# tm7_revE.net
KiCad netlist of a schematic drawn in EAGLE
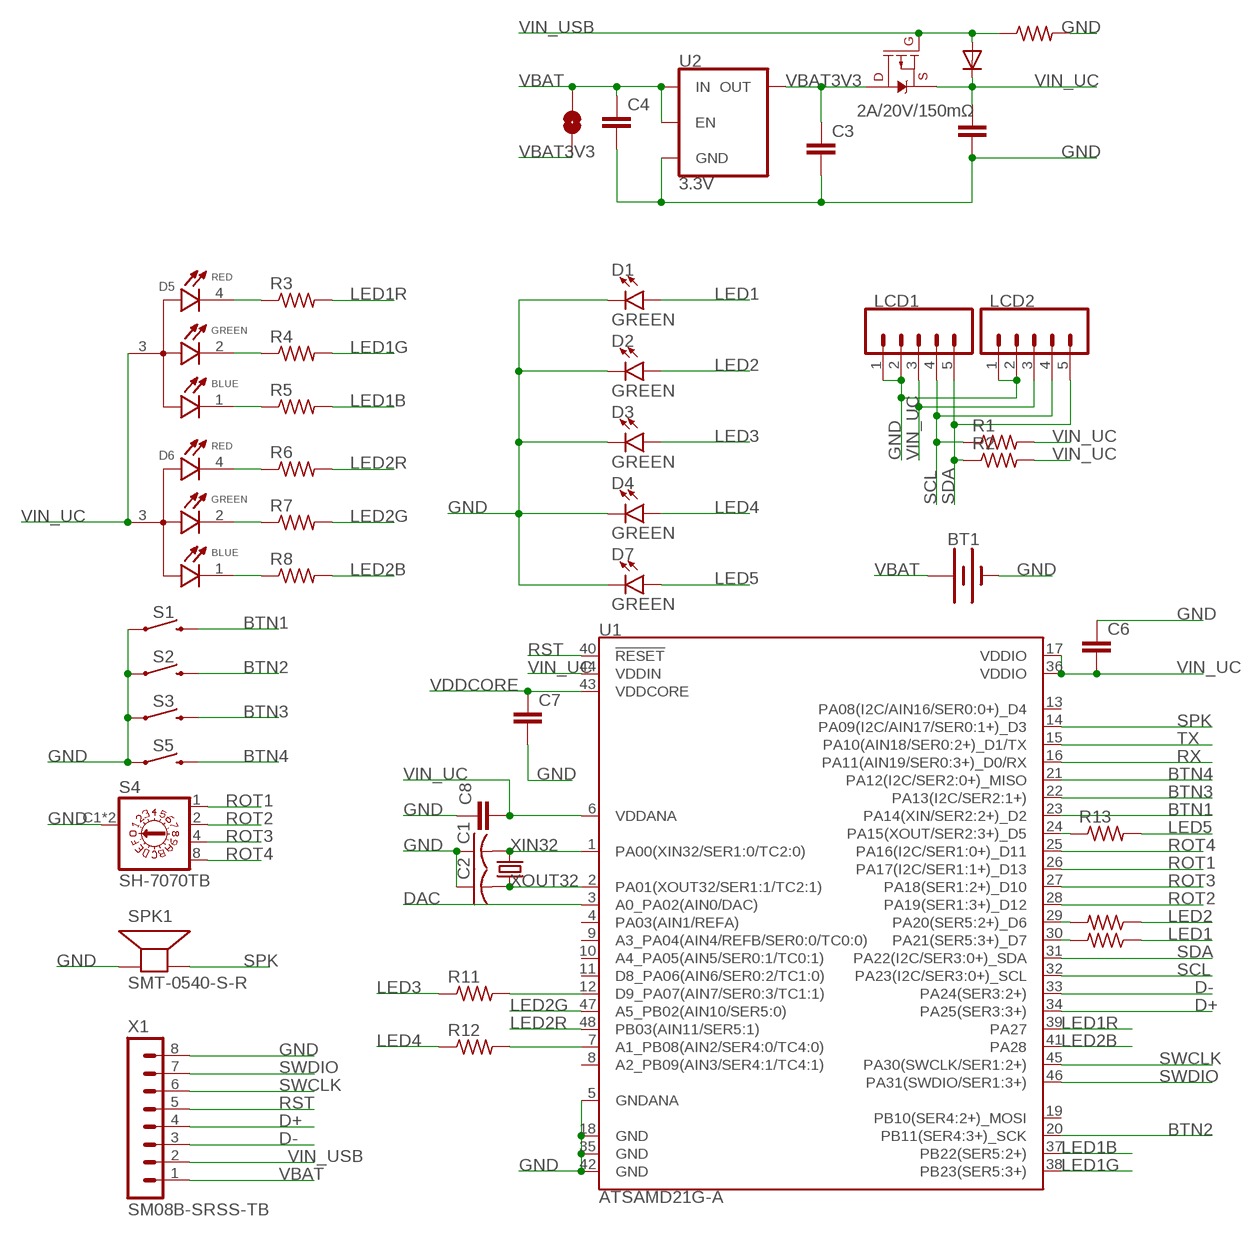
[diagram p0: schematic, sheet 1]

(export (version "E")
  (design (tool "Eeschema 10.0.6"))
  (components
    (comp (ref "BT1")
      (value "BATTERY-20MM_SMD_4LEGS_OVERPASTE_INNER")
      (footprint "eagle-import:BATTCON_20MM_4LEGS_OVERPASTE_INNER")
      (libsource (lib "eagle-import") (part "BATTERY-20MM_SMD_4LEGS_OVERPASTE_INNER"))
    )
    (comp (ref "C1")
      (value "C-USC0603")
      (footprint "eagle-import:C0603")
      (libsource (lib "eagle-import") (part "C-USC0603"))
    )
    (comp (ref "C2")
      (value "C-USC0603")
      (footprint "eagle-import:C0603")
      (libsource (lib "eagle-import") (part "C-USC0603"))
    )
    (comp (ref "C3")
      (value "C-EUC0603")
      (footprint "eagle-import:C0603")
      (libsource (lib "eagle-import") (part "C-EUC0603"))
    )
    (comp (ref "C4")
      (value "C-EUC0603")
      (footprint "eagle-import:C0603")
      (libsource (lib "eagle-import") (part "C-EUC0603"))
    )
    (comp (ref "C6")
      (value "C-EUC0603")
      (footprint "eagle-import:C0603")
      (libsource (lib "eagle-import") (part "C-EUC0603"))
    )
    (comp (ref "C7")
      (value "C-EUC0603")
      (footprint "eagle-import:C0603")
      (libsource (lib "eagle-import") (part "C-EUC0603"))
    )
    (comp (ref "C8")
      (value "C-EUC0603")
      (footprint "eagle-import:C0603")
      (libsource (lib "eagle-import") (part "C-EUC0603"))
    )
    (comp (ref "C9")
      (value "C-EUC0603")
      (footprint "eagle-import:C0603")
      (libsource (lib "eagle-import") (part "C-EUC0603"))
    )
    (comp (ref "D1")
      (value "GREEN")
      (footprint "eagle-import:LED-1206")
      (libsource (lib "eagle-import") (part "LED-GREEN1206"))
    )
    (comp (ref "D2")
      (value "GREEN")
      (footprint "eagle-import:LED-1206")
      (libsource (lib "eagle-import") (part "LED-GREEN1206"))
    )
    (comp (ref "D3")
      (value "GREEN")
      (footprint "eagle-import:LED-1206")
      (libsource (lib "eagle-import") (part "LED-GREEN1206"))
    )
    (comp (ref "D4")
      (value "GREEN")
      (footprint "eagle-import:LED-1206")
      (libsource (lib "eagle-import") (part "LED-GREEN1206"))
    )
    (comp (ref "D5")
      (value "EAST1616RGBA3")
      (footprint "eagle-import:LED_EAST1616RGBA3")
      (fields (field (name "MF") "Everlight Electronics"))
      (libsource (lib "eagle-import") (part "EAST1616RGBA3"))
    )
    (comp (ref "D6")
      (value "EAST1616RGBA3")
      (footprint "eagle-import:LED_EAST1616RGBA3")
      (fields (field (name "MF") "Everlight Electronics"))
      (libsource (lib "eagle-import") (part "EAST1616RGBA3"))
    )
    (comp (ref "D7")
      (value "GREEN")
      (footprint "eagle-import:LED-1206")
      (libsource (lib "eagle-import") (part "LED-GREEN1206"))
    )
    (comp (ref "D8")
      (value "DIODESOD-323F")
      (footprint "eagle-import:SOD-323F")
      (libsource (lib "eagle-import") (part "DIODESOD-323F"))
    )
    (comp (ref "JP1")
      (value "JUMPER-SMT_2_NO_NO-SILK")
      (footprint "eagle-import:SMT-JUMPER_2_NO_NO-SILK")
      (libsource (lib "eagle-import") (part "JUMPER-SMT_2_NO_NO-SILK"))
    )
    (comp (ref "LCD1")
      (value "CONN_05VERT_FEMALE_HEADER")
      (footprint "eagle-import:1X05_SMD_VERTICAL_COMBO")
      (libsource (lib "eagle-import") (part "CONN_05VERT_FEMALE_HEADER"))
    )
    (comp (ref "LCD2")
      (value "CONN_05VERT_FEMALE_HEADER")
      (footprint "eagle-import:1X05_SMD_VERTICAL_COMBO")
      (libsource (lib "eagle-import") (part "CONN_05VERT_FEMALE_HEADER"))
    )
    (comp (ref "Q1")
      (value "2A/20V/150mΩ")
      (footprint "eagle-import:SOT26")
      (libsource (lib "eagle-import") (part "MOSFET_PCH_DUAL-DMP2240UDM"))
    )
    (comp (ref "R1")
      (value "R-US_R0603")
      (footprint "eagle-import:R0603")
      (libsource (lib "eagle-import") (part "rcl_334_R-US_R0603"))
    )
    (comp (ref "R2")
      (value "R-US_R0603")
      (footprint "eagle-import:R0603")
      (libsource (lib "eagle-import") (part "rcl_334_R-US_R0603"))
    )
    (comp (ref "R3")
      (value "R-US_R0603")
      (footprint "eagle-import:R0603")
      (libsource (lib "eagle-import") (part "rcl_334_R-US_R0603"))
    )
    (comp (ref "R4")
      (value "R-US_R0603")
      (footprint "eagle-import:R0603")
      (libsource (lib "eagle-import") (part "rcl_334_R-US_R0603"))
    )
    (comp (ref "R5")
      (value "R-US_R0603")
      (footprint "eagle-import:R0603")
      (libsource (lib "eagle-import") (part "rcl_334_R-US_R0603"))
    )
    (comp (ref "R6")
      (value "R-US_R0603")
      (footprint "eagle-import:R0603")
      (libsource (lib "eagle-import") (part "rcl_334_R-US_R0603"))
    )
    (comp (ref "R7")
      (value "R-US_R0603")
      (footprint "eagle-import:R0603")
      (libsource (lib "eagle-import") (part "rcl_334_R-US_R0603"))
    )
    (comp (ref "R8")
      (value "R-US_R0603")
      (footprint "eagle-import:R0603")
      (libsource (lib "eagle-import") (part "rcl_334_R-US_R0603"))
    )
    (comp (ref "R9")
      (value "R-US_R0603")
      (footprint "eagle-import:R0603")
      (libsource (lib "eagle-import") (part "rcl_334_R-US_R0603"))
    )
    (comp (ref "R10")
      (value "R-US_R0603")
      (footprint "eagle-import:R0603")
      (libsource (lib "eagle-import") (part "rcl_334_R-US_R0603"))
    )
    (comp (ref "R11")
      (value "R-US_R0603")
      (footprint "eagle-import:R0603")
      (libsource (lib "eagle-import") (part "rcl_334_R-US_R0603"))
    )
    (comp (ref "R12")
      (value "R-US_R0603")
      (footprint "eagle-import:R0603")
      (libsource (lib "eagle-import") (part "rcl_334_R-US_R0603"))
    )
    (comp (ref "R13")
      (value "R-US_R0603")
      (footprint "eagle-import:R0603")
      (libsource (lib "eagle-import") (part "rcl_334_R-US_R0603"))
    )
    (comp (ref "R14")
      (value "R-US_R0603")
      (footprint "eagle-import:R0603")
      (libsource (lib "eagle-import") (part "R-US_R0603"))
    )
    (comp (ref "S1")
      (value "MOMENTARY-SWITCH-SPST-SMD-6.0X3.5MM")
      (footprint "eagle-import:TACTILE_SWITCH_SMD_6.0X3.5MM")
      (libsource (lib "eagle-import") (part "MOMENTARY-SWITCH-SPST-SMD-6.0X3.5MM"))
    )
    (comp (ref "S2")
      (value "MOMENTARY-SWITCH-SPST-SMD-6.0X3.5MM")
      (footprint "eagle-import:TACTILE_SWITCH_SMD_6.0X3.5MM")
      (libsource (lib "eagle-import") (part "MOMENTARY-SWITCH-SPST-SMD-6.0X3.5MM"))
    )
    (comp (ref "S3")
      (value "MOMENTARY-SWITCH-SPST-SMD-6.0X3.5MM")
      (footprint "eagle-import:TACTILE_SWITCH_SMD_6.0X3.5MM")
      (libsource (lib "eagle-import") (part "MOMENTARY-SWITCH-SPST-SMD-6.0X3.5MM"))
    )
    (comp (ref "S4")
      (value "SH-7070TB")
      (footprint "eagle-import:SH-7070B")
      (fields (field (name "MF") "Nidec Copal"))
      (libsource (lib "eagle-import") (part "SH-7070TB"))
    )
    (comp (ref "S5")
      (value "MOMENTARY-SWITCH-SPST-SMD-6.0X3.5MM")
      (footprint "eagle-import:TACTILE_SWITCH_SMD_6.0X3.5MM")
      (libsource (lib "eagle-import") (part "MOMENTARY-SWITCH-SPST-SMD-6.0X3.5MM"))
    )
    (comp (ref "SPK1")
      (value "SMT-0540-S-R")
      (footprint "eagle-import:SMT-0540-S-R")
      (fields (field (name "MF") "PUI"))
      (libsource (lib "eagle-import") (part "SMT-0540-S-R"))
    )
    (comp (ref "U1")
      (value "ATSAMD21G-A")
      (footprint "eagle-import:TQFP-48")
      (libsource (lib "eagle-import") (part "ATSAMD21G-A"))
    )
    (comp (ref "U2")
      (value "3.3V")
      (footprint "eagle-import:SOT23-5")
      (libsource (lib "eagle-import") (part "V_REG_AP2112K-3.3V"))
    )
    (comp (ref "X1")
      (value "SM08B-SRSS-TB")
      (footprint "eagle-import:SM08B-SRSS-TB")
      (libsource (lib "eagle-import") (part "SM08B-SRSS-TB"))
    )
    (comp (ref "Y1")
      (value "32.768kHz")
      (footprint "eagle-import:CRYSTAL-SMD-3.2X1.5MM")
      (libsource (lib "eagle-import") (part "CRYSTAL-32.768KHZSMD-3.2X1.5"))
    )
  )
  (nets
    (net (code "1") (name "/BTN1") (class "Default")
      (node (ref "S1") (pin "2") (pinfunction "2_2") (pintype "passive"))
      (node (ref "U1") (pin "23") (pinfunction "PA14(XIN/SER2:2+)_D2_23") (pintype "bidirectional"))
    )
    (net (code "2") (name "/BTN2") (class "Default")
      (node (ref "S2") (pin "2") (pinfunction "2_2") (pintype "passive"))
      (node (ref "U1") (pin "20") (pinfunction "PB11(SER4:3+)_SCK_20") (pintype "bidirectional"))
    )
    (net (code "3") (name "/BTN3") (class "Default")
      (node (ref "S3") (pin "2") (pinfunction "2_2") (pintype "passive"))
      (node (ref "U1") (pin "22") (pinfunction "PA13(I2C/SER2:1+)_22") (pintype "bidirectional"))
    )
    (net (code "4") (name "/BTN4") (class "Default")
      (node (ref "S5") (pin "2") (pinfunction "2_2") (pintype "passive"))
      (node (ref "U1") (pin "21") (pinfunction "PA12(I2C/SER2:0+)_MISO_21") (pintype "bidirectional"))
    )
    (net (code "5") (name "/D+") (class "Default")
      (node (ref "U1") (pin "34") (pinfunction "PA25(SER3:3+)_34") (pintype "bidirectional"))
      (node (ref "X1") (pin "4") (pinfunction "4_4") (pintype "passive"))
    )
    (net (code "6") (name "/D-") (class "Default")
      (node (ref "U1") (pin "33") (pinfunction "PA24(SER3:2+)_33") (pintype "bidirectional"))
      (node (ref "X1") (pin "3") (pinfunction "3_3") (pintype "passive"))
    )
    (net (code "7") (name "/DAC") (class "Default")
      (node (ref "U1") (pin "3") (pinfunction "A0_PA02(AIN0/DAC)_3") (pintype "bidirectional"))
    )
    (net (code "8") (name "/GND") (class "Default")
      (node (ref "BT1") (pin "2") (pinfunction "-_2") (pintype "power_in"))
      (node (ref "C1") (pin "1") (pinfunction "1_1") (pintype "passive"))
      (node (ref "C2") (pin "1") (pinfunction "1_1") (pintype "passive"))
      (node (ref "C3") (pin "2") (pinfunction "2_2") (pintype "passive"))
      (node (ref "C4") (pin "2") (pinfunction "2_2") (pintype "passive"))
      (node (ref "C6") (pin "1") (pinfunction "1_1") (pintype "passive"))
      (node (ref "C7") (pin "2") (pinfunction "2_2") (pintype "passive"))
      (node (ref "C8") (pin "1") (pinfunction "1_1") (pintype "passive"))
      (node (ref "C9") (pin "2") (pinfunction "2_2") (pintype "passive"))
      (node (ref "D1") (pin "C") (pinfunction "C_C") (pintype "passive"))
      (node (ref "D2") (pin "C") (pinfunction "C_C") (pintype "passive"))
      (node (ref "D3") (pin "C") (pinfunction "C_C") (pintype "passive"))
      (node (ref "D4") (pin "C") (pinfunction "C_C") (pintype "passive"))
      (node (ref "D7") (pin "C") (pinfunction "C_C") (pintype "passive"))
      (node (ref "LCD1") (pin "1") (pinfunction "1_1") (pintype "passive"))
      (node (ref "LCD1") (pin "2") (pinfunction "2_2") (pintype "passive"))
      (node (ref "LCD2") (pin "1") (pinfunction "1_1") (pintype "passive"))
      (node (ref "LCD2") (pin "2") (pinfunction "2_2") (pintype "passive"))
      (node (ref "R14") (pin "2") (pinfunction "2_2") (pintype "passive"))
      (node (ref "S1") (pin "1") (pinfunction "1_1") (pintype "passive"))
      (node (ref "S2") (pin "1") (pinfunction "1_1") (pintype "passive"))
      (node (ref "S3") (pin "1") (pinfunction "1_1") (pintype "passive"))
      (node (ref "S4") (pin "C1") (pinfunction "C_C1") (pintype "passive"))
      (node (ref "S4") (pin "C2") (pinfunction "C_C2") (pintype "passive"))
      (node (ref "S5") (pin "1") (pinfunction "1_1") (pintype "passive"))
      (node (ref "SPK1") (pin "-") (pinfunction "+_-") (pintype "passive"))
      (node (ref "U1") (pin "18") (pinfunction "GND_18") (pintype "bidirectional"))
      (node (ref "U1") (pin "35") (pinfunction "GND_35") (pintype "bidirectional"))
      (node (ref "U1") (pin "42") (pinfunction "GND_42") (pintype "bidirectional"))
      (node (ref "U1") (pin "5") (pinfunction "GNDANA_5") (pintype "bidirectional"))
      (node (ref "U2") (pin "2") (pinfunction "GND_2") (pintype "input"))
      (node (ref "X1") (pin "8") (pinfunction "8_8") (pintype "passive"))
    )
    (net (code "9") (name "/LED1") (class "Default")
      (node (ref "D1") (pin "A") (pinfunction "A_A") (pintype "passive"))
      (node (ref "R9") (pin "1") (pinfunction "1_1") (pintype "passive"))
    )
    (net (code "10") (name "/LED1B") (class "Default")
      (node (ref "R5") (pin "2") (pinfunction "2_2") (pintype "passive"))
      (node (ref "U1") (pin "37") (pinfunction "PB22(SER5:2+)_37") (pintype "bidirectional"))
    )
    (net (code "11") (name "/LED1G") (class "Default")
      (node (ref "R4") (pin "2") (pinfunction "2_2") (pintype "passive"))
      (node (ref "U1") (pin "38") (pinfunction "PB23(SER5:3+)_38") (pintype "bidirectional"))
    )
    (net (code "12") (name "/LED1R") (class "Default")
      (node (ref "R3") (pin "2") (pinfunction "2_2") (pintype "passive"))
      (node (ref "U1") (pin "39") (pinfunction "PA27_39") (pintype "bidirectional"))
    )
    (net (code "13") (name "/LED2") (class "Default")
      (node (ref "D2") (pin "A") (pinfunction "A_A") (pintype "passive"))
      (node (ref "R10") (pin "1") (pinfunction "1_1") (pintype "passive"))
    )
    (net (code "14") (name "/LED2B") (class "Default")
      (node (ref "R8") (pin "2") (pinfunction "2_2") (pintype "passive"))
      (node (ref "U1") (pin "41") (pinfunction "PA28_41") (pintype "bidirectional"))
    )
    (net (code "15") (name "/LED2G") (class "Default")
      (node (ref "R7") (pin "2") (pinfunction "2_2") (pintype "passive"))
      (node (ref "U1") (pin "47") (pinfunction "A5_PB02(AIN10/SER5:0)_47") (pintype "bidirectional"))
    )
    (net (code "16") (name "/LED2R") (class "Default")
      (node (ref "R6") (pin "2") (pinfunction "2_2") (pintype "passive"))
      (node (ref "U1") (pin "48") (pinfunction "PB03(AIN11/SER5:1)_48") (pintype "bidirectional"))
    )
    (net (code "17") (name "/LED3") (class "Default")
      (node (ref "D3") (pin "A") (pinfunction "A_A") (pintype "passive"))
      (node (ref "R11") (pin "1") (pinfunction "1_1") (pintype "passive"))
    )
    (net (code "18") (name "/LED4") (class "Default")
      (node (ref "D4") (pin "A") (pinfunction "A_A") (pintype "passive"))
      (node (ref "R12") (pin "1") (pinfunction "1_1") (pintype "passive"))
    )
    (net (code "19") (name "/LED5") (class "Default")
      (node (ref "D7") (pin "A") (pinfunction "A_A") (pintype "passive"))
      (node (ref "R13") (pin "2") (pinfunction "2_2") (pintype "passive"))
    )
    (net (code "20") (name "/ROT1") (class "Default")
      (node (ref "S4") (pin "1") (pinfunction "1_1") (pintype "passive"))
      (node (ref "U1") (pin "26") (pinfunction "PA17(I2C/SER1:1+)_D13_26") (pintype "bidirectional"))
    )
    (net (code "21") (name "/ROT2") (class "Default")
      (node (ref "S4") (pin "2") (pinfunction "2_2") (pintype "passive"))
      (node (ref "U1") (pin "28") (pinfunction "PA19(SER1:3+)_D12_28") (pintype "bidirectional"))
    )
    (net (code "22") (name "/ROT3") (class "Default")
      (node (ref "S4") (pin "4") (pinfunction "4_4") (pintype "passive"))
      (node (ref "U1") (pin "27") (pinfunction "PA18(SER1:2+)_D10_27") (pintype "bidirectional"))
    )
    (net (code "23") (name "/ROT4") (class "Default")
      (node (ref "S4") (pin "8") (pinfunction "8_8") (pintype "passive"))
      (node (ref "U1") (pin "25") (pinfunction "PA16(I2C/SER1:0+)_D11_25") (pintype "bidirectional"))
    )
    (net (code "24") (name "/RST") (class "Default")
      (node (ref "U1") (pin "40") (pinfunction "~{RESET}_40") (pintype "bidirectional"))
      (node (ref "X1") (pin "5") (pinfunction "5_5") (pintype "passive"))
    )
    (net (code "25") (name "/RX") (class "Default")
      (node (ref "U1") (pin "16") (pinfunction "PA11(AIN19/SER0:3+)_D0/RX_16") (pintype "bidirectional"))
    )
    (net (code "26") (name "/SCL") (class "Default")
      (node (ref "LCD1") (pin "4") (pinfunction "4_4") (pintype "passive"))
      (node (ref "LCD2") (pin "4") (pinfunction "4_4") (pintype "passive"))
      (node (ref "R1") (pin "1") (pinfunction "1_1") (pintype "passive"))
      (node (ref "U1") (pin "32") (pinfunction "PA23(I2C/SER3:0+)_SCL_32") (pintype "bidirectional"))
    )
    (net (code "27") (name "/SDA") (class "Default")
      (node (ref "LCD1") (pin "5") (pinfunction "5_5") (pintype "passive"))
      (node (ref "LCD2") (pin "5") (pinfunction "5_5") (pintype "passive"))
      (node (ref "R2") (pin "1") (pinfunction "1_1") (pintype "passive"))
      (node (ref "U1") (pin "31") (pinfunction "PA22(I2C/SER3:0+)_SDA_31") (pintype "bidirectional"))
    )
    (net (code "28") (name "/SPK") (class "Default")
      (node (ref "SPK1") (pin "+") (pinfunction "-_+") (pintype "passive"))
      (node (ref "U1") (pin "14") (pinfunction "PA09(I2C/AIN17/SER0:1+)_D3_14") (pintype "bidirectional"))
    )
    (net (code "29") (name "/SWCLK") (class "Default")
      (node (ref "U1") (pin "45") (pinfunction "PA30(SWCLK/SER1:2+)_45") (pintype "bidirectional"))
      (node (ref "X1") (pin "6") (pinfunction "6_6") (pintype "passive"))
    )
    (net (code "30") (name "/SWDIO") (class "Default")
      (node (ref "U1") (pin "46") (pinfunction "PA31(SWDIO/SER1:3+)_46") (pintype "bidirectional"))
      (node (ref "X1") (pin "7") (pinfunction "7_7") (pintype "passive"))
    )
    (net (code "31") (name "/TX") (class "Default")
      (node (ref "U1") (pin "15") (pinfunction "PA10(AIN18/SER0:2+)_D1/TX_15") (pintype "bidirectional"))
    )
    (net (code "32") (name "/VBAT") (class "Default")
      (node (ref "BT1") (pin "1") (pinfunction "+_1") (pintype "power_in"))
      (node (ref "C4") (pin "1") (pinfunction "1_1") (pintype "passive"))
      (node (ref "JP1") (pin "2") (pinfunction "2_2") (pintype "passive"))
      (node (ref "U2") (pin "1") (pinfunction "IN_1") (pintype "input"))
      (node (ref "U2") (pin "3") (pinfunction "EN_3") (pintype "input"))
      (node (ref "X1") (pin "1") (pinfunction "1_1") (pintype "passive"))
    )
    (net (code "33") (name "/VBAT3V3") (class "Default")
      (node (ref "C3") (pin "1") (pinfunction "1_1") (pintype "passive"))
      (node (ref "JP1") (pin "1") (pinfunction "1_1") (pintype "passive"))
      (node (ref "Q1") (pin "D1") (pinfunction "D_D1") (pintype "bidirectional"))
      (node (ref "U2") (pin "5") (pinfunction "OUT_5") (pintype "passive"))
    )
    (net (code "34") (name "/VDDCORE") (class "Default")
      (node (ref "C7") (pin "1") (pinfunction "1_1") (pintype "passive"))
      (node (ref "U1") (pin "43") (pinfunction "VDDCORE_43") (pintype "bidirectional"))
    )
    (net (code "35") (name "/VIN_UC") (class "Default")
      (node (ref "C6") (pin "2") (pinfunction "2_2") (pintype "passive"))
      (node (ref "C8") (pin "2") (pinfunction "2_2") (pintype "passive"))
      (node (ref "C9") (pin "1") (pinfunction "1_1") (pintype "passive"))
      (node (ref "D5") (pin "3") (pinfunction "A_3") (pintype "passive"))
      (node (ref "D6") (pin "3") (pinfunction "A_3") (pintype "passive"))
      (node (ref "D8") (pin "C") (pinfunction "C_C") (pintype "passive"))
      (node (ref "LCD1") (pin "3") (pinfunction "3_3") (pintype "passive"))
      (node (ref "LCD2") (pin "3") (pinfunction "3_3") (pintype "passive"))
      (node (ref "Q1") (pin "S1") (pinfunction "S_S1") (pintype "bidirectional"))
      (node (ref "R1") (pin "2") (pinfunction "2_2") (pintype "passive"))
      (node (ref "R2") (pin "2") (pinfunction "2_2") (pintype "passive"))
      (node (ref "U1") (pin "17") (pinfunction "VDDIO_17") (pintype "bidirectional"))
      (node (ref "U1") (pin "36") (pinfunction "VDDIO_36") (pintype "bidirectional"))
      (node (ref "U1") (pin "44") (pinfunction "VDDIN_44") (pintype "bidirectional"))
      (node (ref "U1") (pin "6") (pinfunction "VDDANA_6") (pintype "bidirectional"))
    )
    (net (code "36") (name "/VIN_USB") (class "Default")
      (node (ref "D8") (pin "A") (pinfunction "A_A") (pintype "passive"))
      (node (ref "Q1") (pin "G1") (pinfunction "G_G1") (pintype "bidirectional"))
      (node (ref "R14") (pin "1") (pinfunction "1_1") (pintype "passive"))
      (node (ref "X1") (pin "2") (pinfunction "2_2") (pintype "passive"))
    )
    (net (code "37") (name "/XIN32") (class "Default")
      (node (ref "C1") (pin "2") (pinfunction "2_2") (pintype "passive"))
      (node (ref "U1") (pin "1") (pinfunction "PA00(XIN32/SER1:0/TC2:0)_1") (pintype "bidirectional"))
      (node (ref "Y1") (pin "P$2") (pinfunction "2_P$2") (pintype "passive"))
    )
    (net (code "38") (name "/XOUT32") (class "Default")
      (node (ref "C2") (pin "2") (pinfunction "2_2") (pintype "passive"))
      (node (ref "U1") (pin "2") (pinfunction "PA01(XOUT32/SER1:1/TC2:1)_2") (pintype "bidirectional"))
      (node (ref "Y1") (pin "P$1") (pinfunction "1_P$1") (pintype "passive"))
    )
    (net (code "39") (name "Net-(D5-B_C)") (class "Default")
      (node (ref "D5") (pin "1") (pinfunction "B_C_1") (pintype "passive"))
      (node (ref "R5") (pin "1") (pinfunction "1_1") (pintype "passive"))
    )
    (net (code "40") (name "Net-(D5-G_C)") (class "Default")
      (node (ref "D5") (pin "2") (pinfunction "G_C_2") (pintype "passive"))
      (node (ref "R4") (pin "1") (pinfunction "1_1") (pintype "passive"))
    )
    (net (code "41") (name "Net-(D5-R_C)") (class "Default")
      (node (ref "D5") (pin "4") (pinfunction "R_C_4") (pintype "passive"))
      (node (ref "R3") (pin "1") (pinfunction "1_1") (pintype "passive"))
    )
    (net (code "42") (name "Net-(D6-B_C)") (class "Default")
      (node (ref "D6") (pin "1") (pinfunction "B_C_1") (pintype "passive"))
      (node (ref "R8") (pin "1") (pinfunction "1_1") (pintype "passive"))
    )
    (net (code "43") (name "Net-(D6-G_C)") (class "Default")
      (node (ref "D6") (pin "2") (pinfunction "G_C_2") (pintype "passive"))
      (node (ref "R7") (pin "1") (pinfunction "1_1") (pintype "passive"))
    )
    (net (code "44") (name "Net-(D6-R_C)") (class "Default")
      (node (ref "D6") (pin "4") (pinfunction "R_C_4") (pintype "passive"))
      (node (ref "R6") (pin "1") (pinfunction "1_1") (pintype "passive"))
    )
    (net (code "45") (name "Net-(U1-A1_PB08(AIN2{slash}SER4:0{slash}TC4:0))") (class "Default")
      (node (ref "R12") (pin "2") (pinfunction "2_2") (pintype "passive"))
      (node (ref "U1") (pin "7") (pinfunction "A1_PB08(AIN2/SER4:0/TC4:0)_7") (pintype "bidirectional"))
    )
    (net (code "46") (name "Net-(U1-D9_PA07(AIN7{slash}SER0:3{slash}TC1:1))") (class "Default")
      (node (ref "R11") (pin "2") (pinfunction "2_2") (pintype "passive"))
      (node (ref "U1") (pin "12") (pinfunction "D9_PA07(AIN7/SER0:3/TC1:1)_12") (pintype "bidirectional"))
    )
    (net (code "47") (name "Net-(U1-PA15(XOUT{slash}SER2:3+)_D5)") (class "Default")
      (node (ref "R13") (pin "1") (pinfunction "1_1") (pintype "passive"))
      (node (ref "U1") (pin "24") (pinfunction "PA15(XOUT/SER2:3+)_D5_24") (pintype "bidirectional"))
    )
    (net (code "48") (name "Net-(U1-PA20(SER5:2+)_D6)") (class "Default")
      (node (ref "R10") (pin "2") (pinfunction "2_2") (pintype "passive"))
      (node (ref "U1") (pin "29") (pinfunction "PA20(SER5:2+)_D6_29") (pintype "bidirectional"))
    )
    (net (code "49") (name "Net-(U1-PA21(SER5:3+)_D7)") (class "Default")
      (node (ref "R9") (pin "2") (pinfunction "2_2") (pintype "passive"))
      (node (ref "U1") (pin "30") (pinfunction "PA21(SER5:3+)_D7_30") (pintype "bidirectional"))
    )
    (net (code "50") (name "unconnected-(U1-A2_PB09(AIN3{slash}SER4:1{slash}TC4:1)-Pad8)") (class "Default")
      (node (ref "U1") (pin "8") (pinfunction "A2_PB09(AIN3/SER4:1/TC4:1)_8") (pintype "bidirectional"))
    )
    (net (code "51") (name "unconnected-(U1-A3_PA04(AIN4{slash}REFB{slash}SER0:0{slash}TC0:0)-Pad9)") (class "Default")
      (node (ref "U1") (pin "9") (pinfunction "A3_PA04(AIN4/REFB/SER0:0/TC0:0)_9") (pintype "bidirectional"))
    )
    (net (code "52") (name "unconnected-(U1-A4_PA05(AIN5{slash}SER0:1{slash}TC0:1)-Pad10)") (class "Default")
      (node (ref "U1") (pin "10") (pinfunction "A4_PA05(AIN5/SER0:1/TC0:1)_10") (pintype "bidirectional"))
    )
    (net (code "53") (name "unconnected-(U1-D8_PA06(AIN6{slash}SER0:2{slash}TC1:0)-Pad11)") (class "Default")
      (node (ref "U1") (pin "11") (pinfunction "D8_PA06(AIN6/SER0:2/TC1:0)_11") (pintype "bidirectional"))
    )
    (net (code "54") (name "unconnected-(U1-PA03(AIN1{slash}REFA)-Pad4)") (class "Default")
      (node (ref "U1") (pin "4") (pinfunction "PA03(AIN1/REFA)_4") (pintype "bidirectional"))
    )
    (net (code "55") (name "unconnected-(U1-PA08(I2C{slash}AIN16{slash}SER0:0+)_D4-Pad13)") (class "Default")
      (node (ref "U1") (pin "13") (pinfunction "PA08(I2C/AIN16/SER0:0+)_D4_13") (pintype "bidirectional"))
    )
    (net (code "56") (name "unconnected-(U1-PB10(SER4:2+)_MOSI-Pad19)") (class "Default")
      (node (ref "U1") (pin "19") (pinfunction "PB10(SER4:2+)_MOSI_19") (pintype "bidirectional"))
    )
  )
)
